# SeguidorC1_0.net
KiCad netlist of a schematic drawn in EAGLE
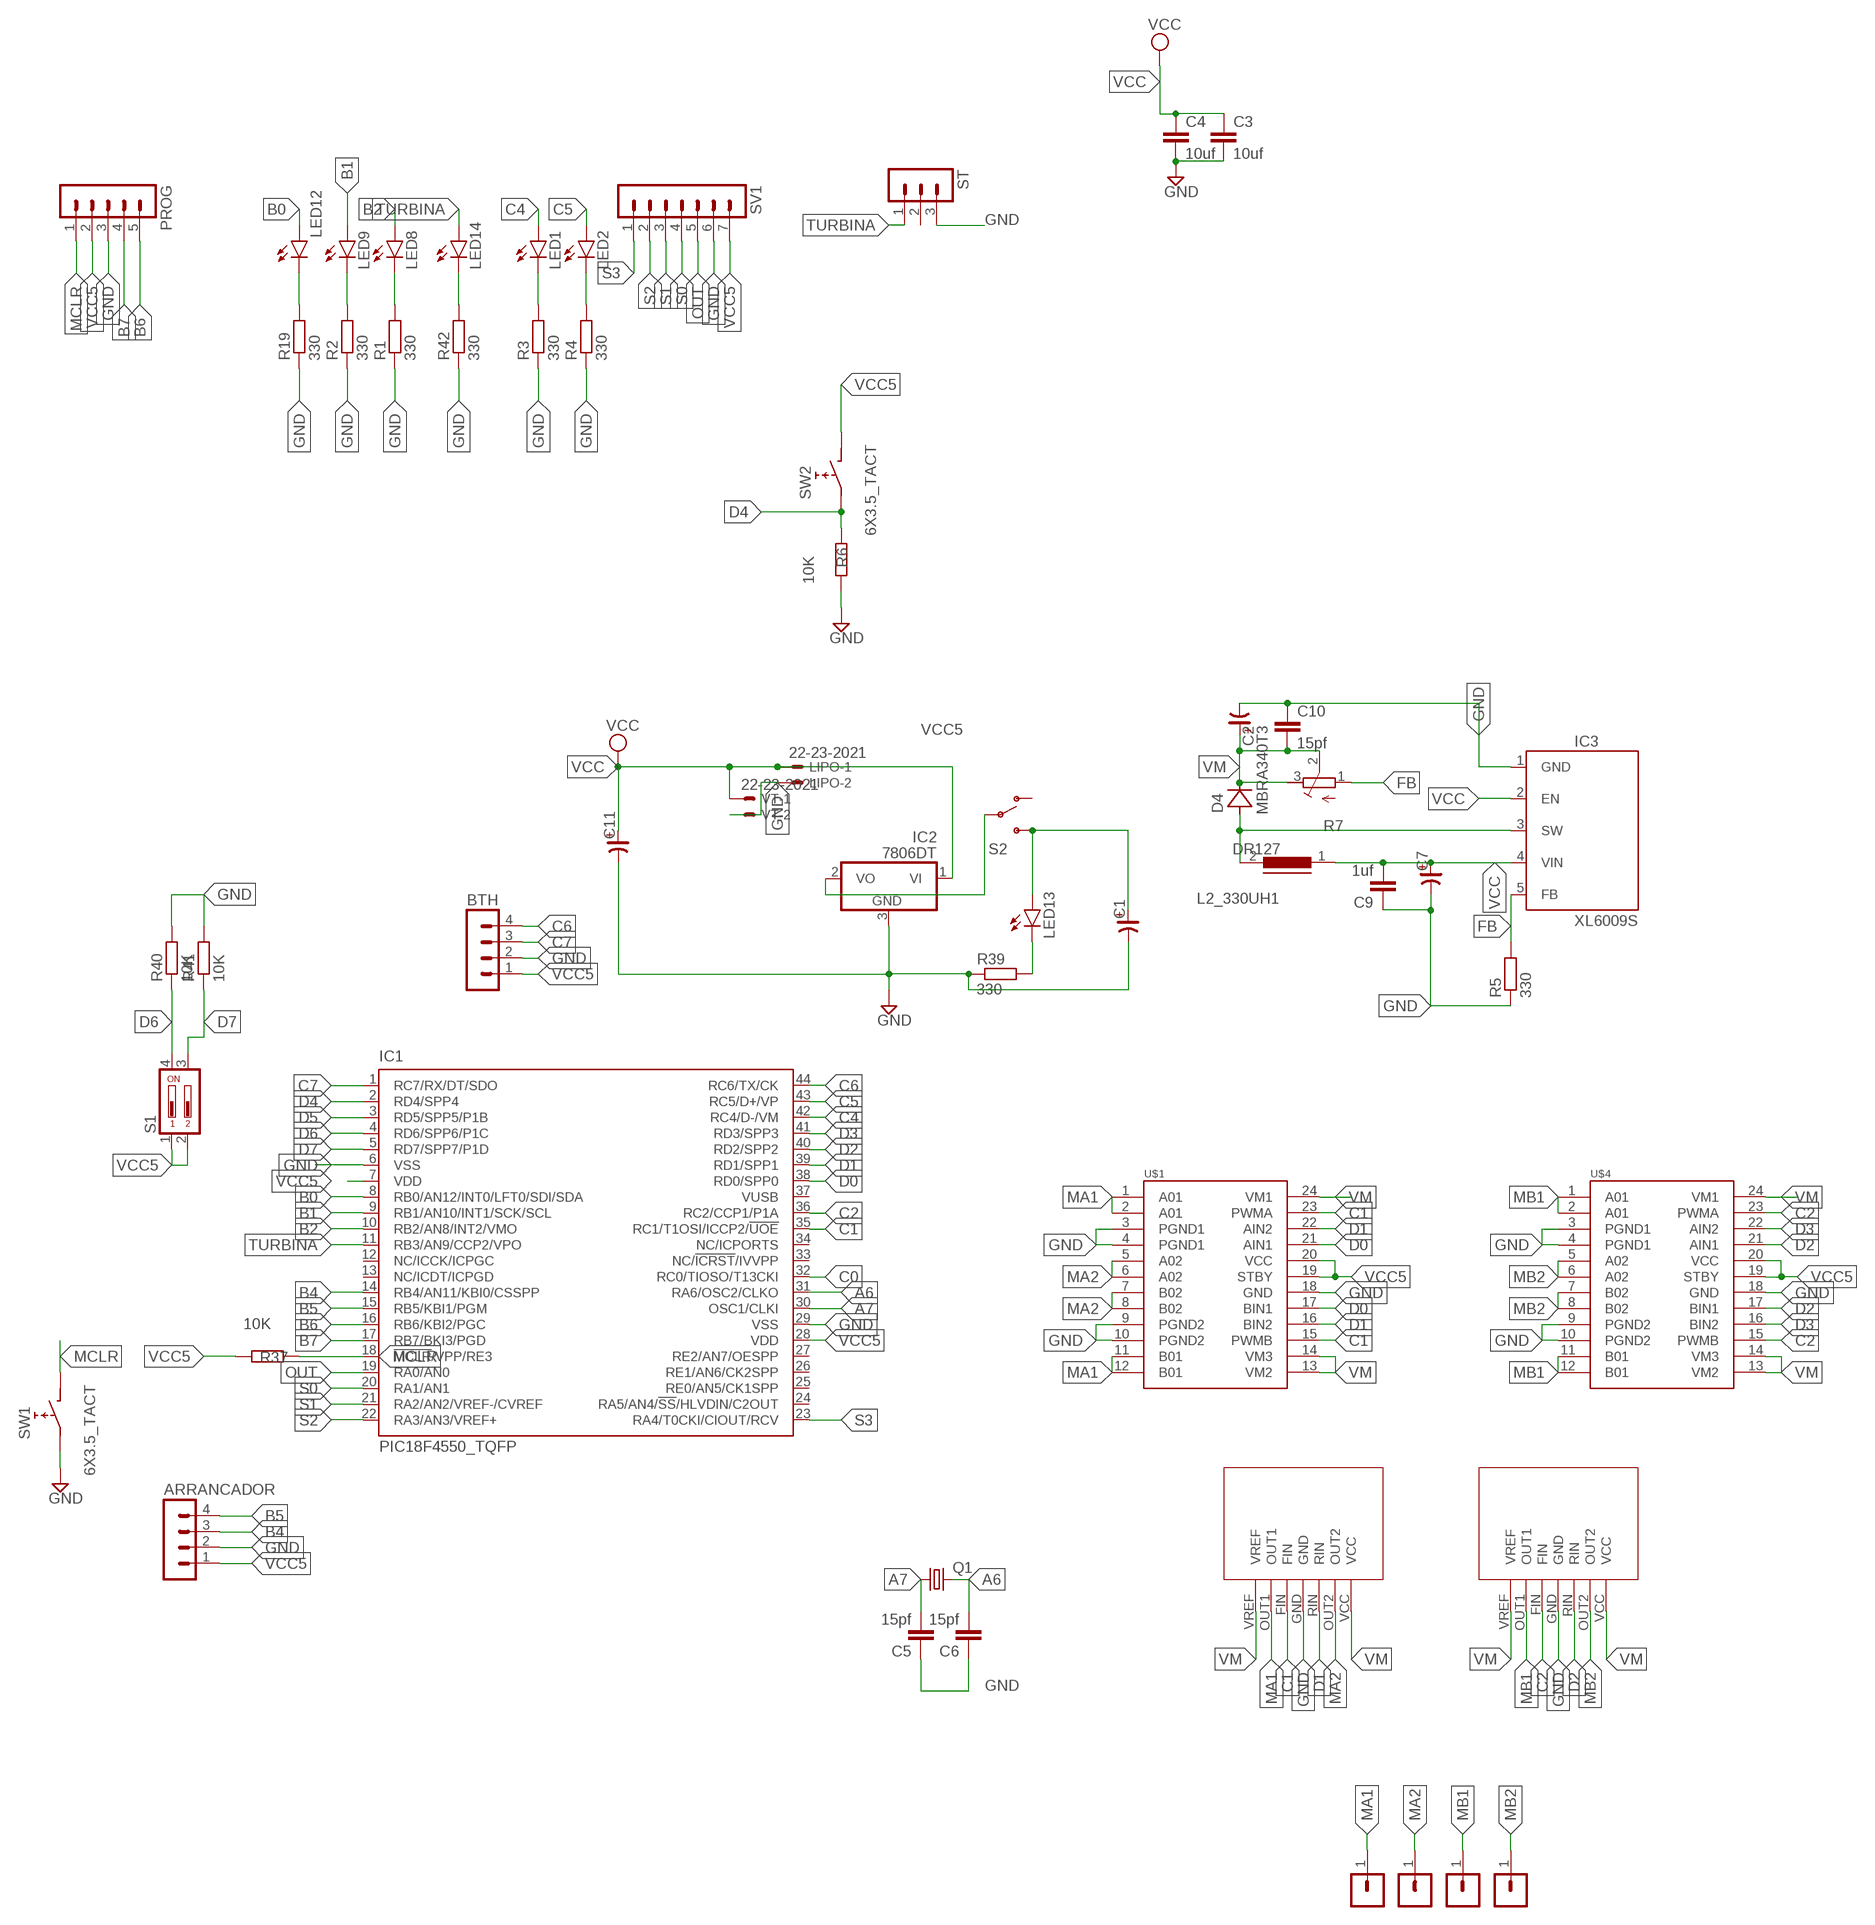
[diagram p0: schematic, sheet 1]

(export (version "E")
  (design (tool "Eeschema 10.0.6"))
  (components
    (comp (ref "ARRANCADOR")
      (value "MA04-1")
      (footprint "eagle-import:MA04-1")
      (libsource (lib "eagle-import") (part "MA04-1"))
    )
    (comp (ref "BTH")
      (value "MA04-1")
      (footprint "eagle-import:MA04-1")
      (libsource (lib "eagle-import") (part "MA04-1"))
    )
    (comp (ref "C1")
      (value "CP_SV-D")
      (footprint "eagle-import:CSV-D")
      (libsource (lib "eagle-import") (part "CP_SV-D"))
    )
    (comp (ref "C2")
      (value "CP_SV-D")
      (footprint "eagle-import:CSV-D")
      (libsource (lib "eagle-import") (part "CP_SV-D"))
    )
    (comp (ref "C3")
      (value "10uf")
      (footprint "eagle-import:C0805")
      (libsource (lib "eagle-import") (part "C-EUC0805"))
    )
    (comp (ref "C4")
      (value "10uf")
      (footprint "eagle-import:C0805")
      (libsource (lib "eagle-import") (part "C-EUC0805"))
    )
    (comp (ref "C5")
      (value "15pf")
      (footprint "eagle-import:C0805")
      (libsource (lib "eagle-import") (part "C-EUC0805"))
    )
    (comp (ref "C6")
      (value "15pf")
      (footprint "eagle-import:C0805")
      (libsource (lib "eagle-import") (part "C-EUC0805"))
    )
    (comp (ref "C7")
      (value "CP_SV-D")
      (footprint "eagle-import:CSV-D")
      (libsource (lib "eagle-import") (part "CP_SV-D"))
    )
    (comp (ref "C9")
      (value "1uf")
      (footprint "eagle-import:C0805")
      (libsource (lib "eagle-import") (part "C-EUC0805"))
    )
    (comp (ref "C10")
      (value "15pf")
      (footprint "eagle-import:C0805")
      (libsource (lib "eagle-import") (part "C-EUC0805"))
    )
    (comp (ref "C11")
      (value "CP_SV-D")
      (footprint "eagle-import:CSV-D")
      (fields (field (name "SPICEPREFIX") "C"))
      (libsource (lib "eagle-import") (part "CP_SV-D"))
    )
    (comp (ref "D4")
      (value "MBRA340T3")
      (footprint "eagle-import:SMA")
      (libsource (lib "eagle-import") (part "MBRA340T3"))
    )
    (comp (ref "IC1")
      (value "PIC18F4550_TQFP")
      (footprint "eagle-import:TQFP44")
      (fields (field (name "MF") "MICROCHIP") (field (name "MPN") "PIC18F4550-I/PT"))
      (libsource (lib "eagle-import") (part "PIC18F4_TQFP550"))
    )
    (comp (ref "IC2")
      (value "7806DT")
      (footprint "eagle-import:TO252")
      (libsource (lib "eagle-import") (part "78DT06"))
    )
    (comp (ref "IC3")
      (value "XL6009S")
      (footprint "eagle-import:TO263-5")
      (libsource (lib "eagle-import") (part "XL6009S"))
    )
    (comp (ref "L2_330UH1")
      (value "DR127")
      (footprint "eagle-import:DR127")
      (libsource (lib "eagle-import") (part "DR127"))
    )
    (comp (ref "LED1")
      (value "LEDCHIP-LED0805")
      (footprint "eagle-import:CHIP-LED0805")
      (libsource (lib "eagle-import") (part "LEDCHIP-LED0805"))
    )
    (comp (ref "LED2")
      (value "LEDCHIP-LED0805")
      (footprint "eagle-import:CHIP-LED0805")
      (libsource (lib "eagle-import") (part "LEDCHIP-LED0805"))
    )
    (comp (ref "LED8")
      (value "LEDCHIP-LED0805")
      (footprint "eagle-import:CHIP-LED0805")
      (libsource (lib "eagle-import") (part "LEDCHIP-LED0805"))
    )
    (comp (ref "LED9")
      (value "LEDCHIP-LED0805")
      (footprint "eagle-import:CHIP-LED0805")
      (libsource (lib "eagle-import") (part "LEDCHIP-LED0805"))
    )
    (comp (ref "LED12")
      (value "LEDCHIP-LED0805")
      (footprint "eagle-import:CHIP-LED0805")
      (libsource (lib "eagle-import") (part "LEDCHIP-LED0805"))
    )
    (comp (ref "LED13")
      (value "LEDCHIP-LED0805")
      (footprint "eagle-import:CHIP-LED0805")
      (libsource (lib "eagle-import") (part "LEDCHIP-LED0805"))
    )
    (comp (ref "LED14")
      (value "LEDCHIP-LED0805")
      (footprint "eagle-import:CHIP-LED0805")
      (libsource (lib "eagle-import") (part "LEDCHIP-LED0805"))
    )
    (comp (ref "LIPO")
      (value "22-23-2021")
      (footprint "eagle-import:22-23-2021")
      (fields (field (name "MF") "MOLEX"))
      (libsource (lib "eagle-import") (part "22-23-2021"))
    )
    (comp (ref "PROG")
      (value "MA05-1")
      (footprint "eagle-import:MA05-1")
      (libsource (lib "eagle-import") (part "MA05-1"))
    )
    (comp (ref "Q1")
      (value "CRYSTALHC49U-V")
      (footprint "eagle-import:HC49U-V")
      (libsource (lib "eagle-import") (part "CRYSTALHC49U-V"))
    )
    (comp (ref "R1")
      (value "330")
      (footprint "eagle-import:R0805")
      (libsource (lib "eagle-import") (part "resistor_348_R-EU_R0805"))
    )
    (comp (ref "R2")
      (value "330")
      (footprint "eagle-import:R0805")
      (libsource (lib "eagle-import") (part "resistor_348_R-EU_R0805"))
    )
    (comp (ref "R3")
      (value "330")
      (footprint "eagle-import:R0805")
      (libsource (lib "eagle-import") (part "resistor_348_R-EU_R0805"))
    )
    (comp (ref "R4")
      (value "330")
      (footprint "eagle-import:R0805")
      (libsource (lib "eagle-import") (part "resistor_348_R-EU_R0805"))
    )
    (comp (ref "R5")
      (value "330")
      (footprint "eagle-import:R0805")
      (libsource (lib "eagle-import") (part "resistor_348_R-EU_R0805"))
    )
    (comp (ref "R6")
      (value "10K")
      (footprint "eagle-import:R0805W")
      (libsource (lib "eagle-import") (part "R-EU_R0805W"))
    )
    (comp (ref "R7")
      (value "R-TRIMM3296W")
      (footprint "eagle-import:RTRIM3296W")
      (libsource (lib "eagle-import") (part "R-TRIMM3296W"))
    )
    (comp (ref "R19")
      (value "330")
      (footprint "eagle-import:R0805")
      (libsource (lib "eagle-import") (part "resistor_348_R-EU_R0805"))
    )
    (comp (ref "R37")
      (value "10K")
      (footprint "eagle-import:R0805W")
      (libsource (lib "eagle-import") (part "R-EU_R0805W"))
    )
    (comp (ref "R39")
      (value "330")
      (footprint "eagle-import:R0805")
      (libsource (lib "eagle-import") (part "resistor_348_R-EU_R0805"))
    )
    (comp (ref "R40")
      (value "10K")
      (footprint "eagle-import:R0805W")
      (libsource (lib "eagle-import") (part "R-EU_R0805W"))
    )
    (comp (ref "R41")
      (value "10K")
      (footprint "eagle-import:R0805W")
      (libsource (lib "eagle-import") (part "R-EU_R0805W"))
    )
    (comp (ref "R42")
      (value "330")
      (footprint "eagle-import:R0805")
      (libsource (lib "eagle-import") (part "resistor_348_R-EU_R0805"))
    )
    (comp (ref "S1")
      (value "DIP02YL")
      (footprint "eagle-import:DIP02YL")
      (libsource (lib "eagle-import") (part "DIP02YL"))
    )
    (comp (ref "S2")
      (value "SWITCH-SPSTPTH")
      (footprint "eagle-import:SWITCH-SPDT")
      (libsource (lib "eagle-import") (part "SWITCH-SPSTPTH"))
    )
    (comp (ref "ST")
      (value "MA03-1")
      (footprint "eagle-import:MA03-1")
      (libsource (lib "eagle-import") (part "MA03-1"))
    )
    (comp (ref "SV1")
      (value "MA07-1")
      (footprint "eagle-import:MA07-1")
      (libsource (lib "eagle-import") (part "MA07-1"))
    )
    (comp (ref "SV3")
      (value "MA01-1")
      (footprint "eagle-import:MA01-1")
      (libsource (lib "eagle-import") (part "MA01-1"))
    )
    (comp (ref "SV4")
      (value "MA01-1")
      (footprint "eagle-import:MA01-1")
      (libsource (lib "eagle-import") (part "MA01-1"))
    )
    (comp (ref "SV5")
      (value "MA01-1")
      (footprint "eagle-import:MA01-1")
      (libsource (lib "eagle-import") (part "MA01-1"))
    )
    (comp (ref "SV6")
      (value "MA01-1")
      (footprint "eagle-import:MA01-1")
      (libsource (lib "eagle-import") (part "MA01-1"))
    )
    (comp (ref "SW1")
      (value "6X3.5_TACT")
      (footprint "eagle-import:TACT_6X3.5")
      (libsource (lib "eagle-import") (part "6X3.5_TACT"))
    )
    (comp (ref "SW2")
      (value "6X3.5_TACT")
      (footprint "eagle-import:TACT_6X3.5")
      (libsource (lib "eagle-import") (part "6X3.5_TACT"))
    )
    (comp (ref "U$1")
      (value "TB6621FNG")
      (footprint "eagle-import:SSOP24")
      (libsource (lib "eagle-import") (part "TB6621FNG"))
    )
    (comp (ref "U$2")
      (value "BD623XXX")
      (footprint "eagle-import:HRP7")
      (libsource (lib "eagle-import") (part "BD623XXX"))
    )
    (comp (ref "U$3")
      (value "BD623XXX")
      (footprint "eagle-import:HRP7")
      (libsource (lib "eagle-import") (part "BD623XXX"))
    )
    (comp (ref "U$4")
      (value "TB6621FNG")
      (footprint "eagle-import:SSOP24")
      (libsource (lib "eagle-import") (part "TB6621FNG"))
    )
    (comp (ref "VT")
      (value "22-23-2021")
      (footprint "eagle-import:22-23-2021")
      (fields (field (name "MF") "MOLEX"))
      (libsource (lib "eagle-import") (part "22-23-2021"))
    )
  )
  (nets
    (net (code "1") (name "A6") (class "Default")
      (node (ref "C6") (pin "2") (pinfunction "2_2") (pintype "passive"))
      (node (ref "IC1") (pin "31") (pinfunction "RA6/OSC2/CLKO_31") (pintype "output"))
      (node (ref "Q1") (pin "2") (pinfunction "2_2") (pintype "passive"))
    )
    (net (code "2") (name "A7") (class "Default")
      (node (ref "C5") (pin "2") (pinfunction "2_2") (pintype "passive"))
      (node (ref "IC1") (pin "30") (pinfunction "OSC1/CLKI_30") (pintype "input"))
      (node (ref "Q1") (pin "1") (pinfunction "1_1") (pintype "passive"))
    )
    (net (code "3") (name "B0") (class "Default")
      (node (ref "IC1") (pin "8") (pinfunction "RB0/AN12/INT0/LFT0/SDI/SDA_8") (pintype "bidirectional"))
      (node (ref "LED12") (pin "A") (pinfunction "A_A") (pintype "passive"))
    )
    (net (code "4") (name "B1") (class "Default")
      (node (ref "IC1") (pin "9") (pinfunction "RB1/AN10/INT1/SCK/SCL_9") (pintype "bidirectional"))
      (node (ref "LED9") (pin "A") (pinfunction "A_A") (pintype "passive"))
    )
    (net (code "5") (name "B2") (class "Default")
      (node (ref "IC1") (pin "10") (pinfunction "RB2/AN8/INT2/VMO_10") (pintype "bidirectional"))
      (node (ref "LED8") (pin "A") (pinfunction "A_A") (pintype "passive"))
    )
    (net (code "6") (name "B4") (class "Default")
      (node (ref "ARRANCADOR") (pin "3") (pinfunction "3_3") (pintype "passive"))
      (node (ref "IC1") (pin "14") (pinfunction "RB4/AN11/KBI0/CSSPP_14") (pintype "bidirectional"))
    )
    (net (code "7") (name "B5") (class "Default")
      (node (ref "ARRANCADOR") (pin "4") (pinfunction "4_4") (pintype "passive"))
      (node (ref "IC1") (pin "15") (pinfunction "RB5/KBI1/PGM_15") (pintype "bidirectional"))
    )
    (net (code "8") (name "B6") (class "Default")
      (node (ref "IC1") (pin "16") (pinfunction "RB6/KBI2/PGC_16") (pintype "bidirectional"))
      (node (ref "PROG") (pin "5") (pinfunction "5_5") (pintype "passive"))
    )
    (net (code "9") (name "B7") (class "Default")
      (node (ref "IC1") (pin "17") (pinfunction "RB7/BKI3/PGD_17") (pintype "bidirectional"))
      (node (ref "PROG") (pin "4") (pinfunction "4_4") (pintype "passive"))
    )
    (net (code "10") (name "C0") (class "Default")
      (node (ref "IC1") (pin "32") (pinfunction "RC0/TIOSO/T13CKI_32") (pintype "bidirectional"))
    )
    (net (code "11") (name "C1") (class "Default")
      (node (ref "IC1") (pin "35") (pinfunction "RC1/T1OSI/ICCP2/~{UOE}_35") (pintype "bidirectional"))
      (node (ref "U$1") (pin "15") (pinfunction "PWMB_15") (pintype "bidirectional"))
      (node (ref "U$1") (pin "23") (pinfunction "PWMA_23") (pintype "bidirectional"))
      (node (ref "U$2") (pin "FIN") (pinfunction "FIN_FIN") (pintype "bidirectional"))
    )
    (net (code "12") (name "C2") (class "Default")
      (node (ref "IC1") (pin "36") (pinfunction "RC2/CCP1/P1A_36") (pintype "bidirectional"))
      (node (ref "U$3") (pin "FIN") (pinfunction "FIN_FIN") (pintype "bidirectional"))
      (node (ref "U$4") (pin "15") (pinfunction "PWMB_15") (pintype "bidirectional"))
      (node (ref "U$4") (pin "23") (pinfunction "PWMA_23") (pintype "bidirectional"))
    )
    (net (code "13") (name "C4") (class "Default")
      (node (ref "IC1") (pin "42") (pinfunction "RC4/D-/VM_42") (pintype "bidirectional"))
      (node (ref "LED1") (pin "A") (pinfunction "A_A") (pintype "passive"))
    )
    (net (code "14") (name "C5") (class "Default")
      (node (ref "IC1") (pin "43") (pinfunction "RC5/D+/VP_43") (pintype "bidirectional"))
      (node (ref "LED2") (pin "A") (pinfunction "A_A") (pintype "passive"))
    )
    (net (code "15") (name "C6") (class "Default")
      (node (ref "BTH") (pin "4") (pinfunction "4_4") (pintype "passive"))
      (node (ref "IC1") (pin "44") (pinfunction "RC6/TX/CK_44") (pintype "bidirectional"))
    )
    (net (code "16") (name "C7") (class "Default")
      (node (ref "BTH") (pin "3") (pinfunction "3_3") (pintype "passive"))
      (node (ref "IC1") (pin "1") (pinfunction "RC7/RX/DT/SDO_1") (pintype "bidirectional"))
    )
    (net (code "17") (name "D0") (class "Default")
      (node (ref "IC1") (pin "38") (pinfunction "RD0/SPP0_38") (pintype "bidirectional"))
      (node (ref "U$1") (pin "17") (pinfunction "BIN1_17") (pintype "bidirectional"))
      (node (ref "U$1") (pin "21") (pinfunction "AIN1_21") (pintype "bidirectional"))
    )
    (net (code "18") (name "D1") (class "Default")
      (node (ref "IC1") (pin "39") (pinfunction "RD1/SPP1_39") (pintype "bidirectional"))
      (node (ref "U$1") (pin "16") (pinfunction "BIN2_16") (pintype "bidirectional"))
      (node (ref "U$1") (pin "22") (pinfunction "AIN2_22") (pintype "bidirectional"))
      (node (ref "U$2") (pin "RIN") (pinfunction "RIN_RIN") (pintype "bidirectional"))
    )
    (net (code "19") (name "D2") (class "Default")
      (node (ref "IC1") (pin "40") (pinfunction "RD2/SPP2_40") (pintype "bidirectional"))
      (node (ref "U$3") (pin "RIN") (pinfunction "RIN_RIN") (pintype "bidirectional"))
      (node (ref "U$4") (pin "17") (pinfunction "BIN1_17") (pintype "bidirectional"))
      (node (ref "U$4") (pin "21") (pinfunction "AIN1_21") (pintype "bidirectional"))
    )
    (net (code "20") (name "D3") (class "Default")
      (node (ref "IC1") (pin "41") (pinfunction "RD3/SPP3_41") (pintype "bidirectional"))
      (node (ref "U$4") (pin "16") (pinfunction "BIN2_16") (pintype "bidirectional"))
      (node (ref "U$4") (pin "22") (pinfunction "AIN2_22") (pintype "bidirectional"))
    )
    (net (code "21") (name "D4") (class "Default")
      (node (ref "IC1") (pin "2") (pinfunction "RD4/SPP4_2") (pintype "bidirectional"))
      (node (ref "R6") (pin "2") (pinfunction "2_2") (pintype "passive"))
      (node (ref "SW2") (pin "P$1") (pinfunction "1_P$1") (pintype "passive"))
    )
    (net (code "22") (name "D5") (class "Default")
      (node (ref "IC1") (pin "3") (pinfunction "RD5/SPP5/P1B_3") (pintype "bidirectional"))
    )
    (net (code "23") (name "D6") (class "Default")
      (node (ref "IC1") (pin "4") (pinfunction "RD6/SPP6/P1C_4") (pintype "bidirectional"))
      (node (ref "R40") (pin "1") (pinfunction "1_1") (pintype "passive"))
      (node (ref "S1") (pin "4") (pinfunction "4_4") (pintype "passive"))
    )
    (net (code "24") (name "D7") (class "Default")
      (node (ref "IC1") (pin "5") (pinfunction "RD7/SPP7/P1D_5") (pintype "bidirectional"))
      (node (ref "R41") (pin "1") (pinfunction "1_1") (pintype "passive"))
      (node (ref "S1") (pin "3") (pinfunction "3_3") (pintype "passive"))
    )
    (net (code "25") (name "FB") (class "Default")
      (node (ref "IC3") (pin "5") (pinfunction "FB_5") (pintype "output"))
      (node (ref "R5") (pin "2") (pinfunction "2_2") (pintype "passive"))
      (node (ref "R7") (pin "1") (pinfunction "A_1") (pintype "passive"))
    )
    (net (code "26") (name "GND") (class "Default")
      (node (ref "ARRANCADOR") (pin "2") (pinfunction "2_2") (pintype "passive"))
      (node (ref "BTH") (pin "2") (pinfunction "2_2") (pintype "passive"))
      (node (ref "C1") (pin "-") (pinfunction "-_-") (pintype "passive"))
      (node (ref "C10") (pin "1") (pinfunction "1_1") (pintype "passive"))
      (node (ref "C11") (pin "-") (pinfunction "-_-") (pintype "passive"))
      (node (ref "C2") (pin "-") (pinfunction "-_-") (pintype "passive"))
      (node (ref "C3") (pin "2") (pinfunction "2_2") (pintype "passive"))
      (node (ref "C4") (pin "2") (pinfunction "2_2") (pintype "passive"))
      (node (ref "C5") (pin "1") (pinfunction "1_1") (pintype "passive"))
      (node (ref "C6") (pin "1") (pinfunction "1_1") (pintype "passive"))
      (node (ref "C7") (pin "-") (pinfunction "-_-") (pintype "passive"))
      (node (ref "C9") (pin "1") (pinfunction "1_1") (pintype "passive"))
      (node (ref "IC1") (pin "29") (pinfunction "VSS_29") (pintype "power_in"))
      (node (ref "IC1") (pin "6") (pinfunction "VSS_6") (pintype "power_in"))
      (node (ref "IC2") (pin "3") (pinfunction "GND_3") (pintype "passive"))
      (node (ref "IC3") (pin "1") (pinfunction "GND_1") (pintype "input"))
      (node (ref "LIPO") (pin "2") (pinfunction "S_2") (pintype "passive"))
      (node (ref "PROG") (pin "3") (pinfunction "3_3") (pintype "passive"))
      (node (ref "R1") (pin "1") (pinfunction "1_1") (pintype "passive"))
      (node (ref "R19") (pin "1") (pinfunction "1_1") (pintype "passive"))
      (node (ref "R2") (pin "1") (pinfunction "1_1") (pintype "passive"))
      (node (ref "R3") (pin "1") (pinfunction "1_1") (pintype "passive"))
      (node (ref "R39") (pin "1") (pinfunction "1_1") (pintype "passive"))
      (node (ref "R4") (pin "1") (pinfunction "1_1") (pintype "passive"))
      (node (ref "R40") (pin "2") (pinfunction "2_2") (pintype "passive"))
      (node (ref "R41") (pin "2") (pinfunction "2_2") (pintype "passive"))
      (node (ref "R42") (pin "1") (pinfunction "1_1") (pintype "passive"))
      (node (ref "R5") (pin "1") (pinfunction "1_1") (pintype "passive"))
      (node (ref "R6") (pin "1") (pinfunction "1_1") (pintype "passive"))
      (node (ref "ST") (pin "3") (pinfunction "3_3") (pintype "passive"))
      (node (ref "SV1") (pin "6") (pinfunction "6_6") (pintype "passive"))
      (node (ref "SW1") (pin "P$1") (pinfunction "1_P$1") (pintype "passive"))
      (node (ref "U$1") (pin "10") (pinfunction "PGND2_10") (pintype "bidirectional"))
      (node (ref "U$1") (pin "18") (pinfunction "GND_18") (pintype "bidirectional"))
      (node (ref "U$1") (pin "3") (pinfunction "PGND1_3") (pintype "bidirectional"))
      (node (ref "U$1") (pin "4") (pinfunction "PGND1_4") (pintype "bidirectional"))
      (node (ref "U$1") (pin "9") (pinfunction "PGND2_9") (pintype "bidirectional"))
      (node (ref "U$2") (pin "GND") (pinfunction "GND_GND") (pintype "bidirectional"))
      (node (ref "U$3") (pin "GND") (pinfunction "GND_GND") (pintype "bidirectional"))
      (node (ref "U$4") (pin "10") (pinfunction "PGND2_10") (pintype "bidirectional"))
      (node (ref "U$4") (pin "18") (pinfunction "GND_18") (pintype "bidirectional"))
      (node (ref "U$4") (pin "3") (pinfunction "PGND1_3") (pintype "bidirectional"))
      (node (ref "U$4") (pin "4") (pinfunction "PGND1_4") (pintype "bidirectional"))
      (node (ref "U$4") (pin "9") (pinfunction "PGND2_9") (pintype "bidirectional"))
      (node (ref "VT") (pin "2") (pinfunction "S_2") (pintype "passive"))
    )
    (net (code "27") (name "MA1") (class "Default")
      (node (ref "SV3") (pin "1") (pinfunction "3_1") (pintype "passive"))
      (node (ref "U$1") (pin "1") (pinfunction "A01_1") (pintype "bidirectional"))
      (node (ref "U$1") (pin "11") (pinfunction "B01_11") (pintype "bidirectional"))
      (node (ref "U$1") (pin "12") (pinfunction "B01_12") (pintype "bidirectional"))
      (node (ref "U$1") (pin "2") (pinfunction "A01_2") (pintype "bidirectional"))
      (node (ref "U$2") (pin "OUT1") (pinfunction "OUT1_OUT1") (pintype "bidirectional"))
    )
    (net (code "28") (name "MA2") (class "Default")
      (node (ref "SV4") (pin "1") (pinfunction "3_1") (pintype "passive"))
      (node (ref "U$1") (pin "5") (pinfunction "A02_5") (pintype "bidirectional"))
      (node (ref "U$1") (pin "6") (pinfunction "A02_6") (pintype "bidirectional"))
      (node (ref "U$1") (pin "7") (pinfunction "B02_7") (pintype "bidirectional"))
      (node (ref "U$1") (pin "8") (pinfunction "B02_8") (pintype "bidirectional"))
      (node (ref "U$2") (pin "OUT2") (pinfunction "OUT2_OUT2") (pintype "bidirectional"))
    )
    (net (code "29") (name "MB1") (class "Default")
      (node (ref "SV5") (pin "1") (pinfunction "3_1") (pintype "passive"))
      (node (ref "U$3") (pin "OUT1") (pinfunction "OUT1_OUT1") (pintype "bidirectional"))
      (node (ref "U$4") (pin "1") (pinfunction "A01_1") (pintype "bidirectional"))
      (node (ref "U$4") (pin "11") (pinfunction "B01_11") (pintype "bidirectional"))
      (node (ref "U$4") (pin "12") (pinfunction "B01_12") (pintype "bidirectional"))
      (node (ref "U$4") (pin "2") (pinfunction "A01_2") (pintype "bidirectional"))
    )
    (net (code "30") (name "MB2") (class "Default")
      (node (ref "SV6") (pin "1") (pinfunction "3_1") (pintype "passive"))
      (node (ref "U$3") (pin "OUT2") (pinfunction "OUT2_OUT2") (pintype "bidirectional"))
      (node (ref "U$4") (pin "5") (pinfunction "A02_5") (pintype "bidirectional"))
      (node (ref "U$4") (pin "6") (pinfunction "A02_6") (pintype "bidirectional"))
      (node (ref "U$4") (pin "7") (pinfunction "B02_7") (pintype "bidirectional"))
      (node (ref "U$4") (pin "8") (pinfunction "B02_8") (pintype "bidirectional"))
    )
    (net (code "31") (name "MCLR") (class "Default")
      (node (ref "IC1") (pin "18") (pinfunction "~{MCLR}/VPP/RE3_18") (pintype "input"))
      (node (ref "PROG") (pin "1") (pinfunction "1_1") (pintype "passive"))
      (node (ref "R37") (pin "2") (pinfunction "2_2") (pintype "passive"))
      (node (ref "SW1") (pin "P$2") (pinfunction "2_P$2") (pintype "passive"))
    )
    (net (code "32") (name "Net-(IC2-VO)") (class "Default")
      (node (ref "IC2") (pin "2") (pinfunction "VO_2") (pintype "passive"))
      (node (ref "S2") (pin "2") (pinfunction "P_2") (pintype "passive"))
    )
    (net (code "33") (name "Net-(IC3-SW)") (class "Default")
      (node (ref "D4") (pin "A") (pinfunction "A_A") (pintype "passive"))
      (node (ref "IC3") (pin "3") (pinfunction "SW_3") (pintype "power_in"))
      (node (ref "L2_330UH1") (pin "2") (pinfunction "2_2") (pintype "passive"))
    )
    (net (code "34") (name "Net-(LED1-PadC)") (class "Default")
      (node (ref "LED1") (pin "C") (pinfunction "C_C") (pintype "passive"))
      (node (ref "R3") (pin "2") (pinfunction "2_2") (pintype "passive"))
    )
    (net (code "35") (name "Net-(LED2-PadC)") (class "Default")
      (node (ref "LED2") (pin "C") (pinfunction "C_C") (pintype "passive"))
      (node (ref "R4") (pin "2") (pinfunction "2_2") (pintype "passive"))
    )
    (net (code "36") (name "Net-(LED8-PadC)") (class "Default")
      (node (ref "LED8") (pin "C") (pinfunction "C_C") (pintype "passive"))
      (node (ref "R1") (pin "2") (pinfunction "2_2") (pintype "passive"))
    )
    (net (code "37") (name "Net-(LED9-PadC)") (class "Default")
      (node (ref "LED9") (pin "C") (pinfunction "C_C") (pintype "passive"))
      (node (ref "R2") (pin "2") (pinfunction "2_2") (pintype "passive"))
    )
    (net (code "38") (name "Net-(LED12-PadC)") (class "Default")
      (node (ref "LED12") (pin "C") (pinfunction "C_C") (pintype "passive"))
      (node (ref "R19") (pin "2") (pinfunction "2_2") (pintype "passive"))
    )
    (net (code "39") (name "Net-(LED13-PadC)") (class "Default")
      (node (ref "LED13") (pin "C") (pinfunction "C_C") (pintype "passive"))
      (node (ref "R39") (pin "2") (pinfunction "2_2") (pintype "passive"))
    )
    (net (code "40") (name "Net-(LED14-PadC)") (class "Default")
      (node (ref "LED14") (pin "C") (pinfunction "C_C") (pintype "passive"))
      (node (ref "R42") (pin "2") (pinfunction "2_2") (pintype "passive"))
    )
    (net (code "41") (name "OUT") (class "Default")
      (node (ref "IC1") (pin "19") (pinfunction "RA0/AN0_19") (pintype "bidirectional"))
      (node (ref "SV1") (pin "5") (pinfunction "5_5") (pintype "passive"))
    )
    (net (code "42") (name "S0") (class "Default")
      (node (ref "IC1") (pin "20") (pinfunction "RA1/AN1_20") (pintype "bidirectional"))
      (node (ref "SV1") (pin "4") (pinfunction "4_4") (pintype "passive"))
    )
    (net (code "43") (name "S1") (class "Default")
      (node (ref "IC1") (pin "21") (pinfunction "RA2/AN2/VREF-/CVREF_21") (pintype "bidirectional"))
      (node (ref "SV1") (pin "3") (pinfunction "3_3") (pintype "passive"))
    )
    (net (code "44") (name "S2") (class "Default")
      (node (ref "IC1") (pin "22") (pinfunction "RA3/AN3/VREF+_22") (pintype "bidirectional"))
      (node (ref "SV1") (pin "2") (pinfunction "2_2") (pintype "passive"))
    )
    (net (code "45") (name "S3") (class "Default")
      (node (ref "IC1") (pin "23") (pinfunction "RA4/T0CKI/CIOUT/RCV_23") (pintype "bidirectional"))
      (node (ref "SV1") (pin "1") (pinfunction "1_1") (pintype "passive"))
    )
    (net (code "46") (name "TURBINA") (class "Default")
      (node (ref "IC1") (pin "11") (pinfunction "RB3/AN9/CCP2/VPO_11") (pintype "bidirectional"))
      (node (ref "LED14") (pin "A") (pinfunction "A_A") (pintype "passive"))
      (node (ref "ST") (pin "1") (pinfunction "1_1") (pintype "passive"))
    )
    (net (code "47") (name "VCC") (class "Default")
      (node (ref "C11") (pin "+") (pinfunction "+_+") (pintype "passive"))
      (node (ref "C3") (pin "1") (pinfunction "1_1") (pintype "passive"))
      (node (ref "C4") (pin "1") (pinfunction "1_1") (pintype "passive"))
      (node (ref "C7") (pin "+") (pinfunction "+_+") (pintype "passive"))
      (node (ref "C9") (pin "2") (pinfunction "2_2") (pintype "passive"))
      (node (ref "IC2") (pin "1") (pinfunction "VI_1") (pintype "input"))
      (node (ref "IC3") (pin "2") (pinfunction "EN_2") (pintype "input"))
      (node (ref "IC3") (pin "4") (pinfunction "VIN_4") (pintype "power_in"))
      (node (ref "L2_330UH1") (pin "1") (pinfunction "1_1") (pintype "passive"))
      (node (ref "LIPO") (pin "1") (pinfunction "S_1") (pintype "passive"))
      (node (ref "VT") (pin "1") (pinfunction "S_1") (pintype "passive"))
    )
    (net (code "48") (name "VCC5") (class "Default")
      (node (ref "ARRANCADOR") (pin "1") (pinfunction "1_1") (pintype "passive"))
      (node (ref "BTH") (pin "1") (pinfunction "1_1") (pintype "passive"))
      (node (ref "C1") (pin "+") (pinfunction "+_+") (pintype "passive"))
      (node (ref "IC1") (pin "28") (pinfunction "VDD_28") (pintype "power_in"))
      (node (ref "IC1") (pin "7") (pinfunction "VDD_7") (pintype "power_in"))
      (node (ref "LED13") (pin "A") (pinfunction "A_A") (pintype "passive"))
      (node (ref "PROG") (pin "2") (pinfunction "2_2") (pintype "passive"))
      (node (ref "R37") (pin "1") (pinfunction "1_1") (pintype "passive"))
      (node (ref "S1") (pin "1") (pinfunction "1_1") (pintype "passive"))
      (node (ref "S1") (pin "2") (pinfunction "2_2") (pintype "passive"))
      (node (ref "S2") (pin "3") (pinfunction "S_3") (pintype "passive"))
      (node (ref "SV1") (pin "7") (pinfunction "7_7") (pintype "passive"))
      (node (ref "SW2") (pin "P$2") (pinfunction "2_P$2") (pintype "passive"))
      (node (ref "U$1") (pin "19") (pinfunction "STBY_19") (pintype "bidirectional"))
      (node (ref "U$1") (pin "20") (pinfunction "VCC_20") (pintype "bidirectional"))
      (node (ref "U$4") (pin "19") (pinfunction "STBY_19") (pintype "bidirectional"))
      (node (ref "U$4") (pin "20") (pinfunction "VCC_20") (pintype "bidirectional"))
    )
    (net (code "49") (name "VM") (class "Default")
      (node (ref "C10") (pin "2") (pinfunction "2_2") (pintype "passive"))
      (node (ref "C2") (pin "+") (pinfunction "+_+") (pintype "passive"))
      (node (ref "D4") (pin "C") (pinfunction "C_C") (pintype "passive"))
      (node (ref "R7") (pin "2") (pinfunction "S_2") (pintype "passive"))
      (node (ref "R7") (pin "3") (pinfunction "E_3") (pintype "passive"))
      (node (ref "U$1") (pin "13") (pinfunction "VM2_13") (pintype "bidirectional"))
      (node (ref "U$1") (pin "14") (pinfunction "VM3_14") (pintype "bidirectional"))
      (node (ref "U$1") (pin "24") (pinfunction "VM1_24") (pintype "bidirectional"))
      (node (ref "U$2") (pin "VCC") (pinfunction "VCC_VCC") (pintype "bidirectional"))
      (node (ref "U$2") (pin "VREF") (pinfunction "VREF_VREF") (pintype "bidirectional"))
      (node (ref "U$3") (pin "VCC") (pinfunction "VCC_VCC") (pintype "bidirectional"))
      (node (ref "U$3") (pin "VREF") (pinfunction "VREF_VREF") (pintype "bidirectional"))
      (node (ref "U$4") (pin "13") (pinfunction "VM2_13") (pintype "bidirectional"))
      (node (ref "U$4") (pin "14") (pinfunction "VM3_14") (pintype "bidirectional"))
      (node (ref "U$4") (pin "24") (pinfunction "VM1_24") (pintype "bidirectional"))
    )
    (net (code "50") (name "unconnected-(IC1-NC{slash}ICCK{slash}ICPGC-Pad12)") (class "Default")
      (node (ref "IC1") (pin "12") (pinfunction "NC/ICCK/ICPGC_12") (pintype "bidirectional"))
    )
    (net (code "51") (name "unconnected-(IC1-NC{slash}ICDT{slash}ICPGD-Pad13)") (class "Default")
      (node (ref "IC1") (pin "13") (pinfunction "NC/ICDT/ICPGD_13") (pintype "bidirectional"))
    )
    (net (code "52") (name "unconnected-(IC1-NC{slash}ICPORTS-Pad34)") (class "Default")
      (node (ref "IC1") (pin "34") (pinfunction "NC/ICPORTS_34") (pintype "input"))
    )
    (net (code "53") (name "unconnected-(IC1-NC{slash}~{ICRST}{slash}IVVPP-Pad33)") (class "Default")
      (node (ref "IC1") (pin "33") (pinfunction "NC/~{ICRST}/IVVPP_33") (pintype "input"))
    )
    (net (code "54") (name "unconnected-(IC1-RA5{slash}AN4{slash}~{SS}{slash}HLVDIN{slash}C2OUT-Pad24)") (class "Default")
      (node (ref "IC1") (pin "24") (pinfunction "RA5/AN4/~{SS}/HLVDIN/C2OUT_24") (pintype "bidirectional"))
    )
    (net (code "55") (name "unconnected-(IC1-RE0{slash}AN5{slash}CK1SPP-Pad25)") (class "Default")
      (node (ref "IC1") (pin "25") (pinfunction "RE0/AN5/CK1SPP_25") (pintype "bidirectional"))
    )
    (net (code "56") (name "unconnected-(IC1-RE1{slash}AN6{slash}CK2SPP-Pad26)") (class "Default")
      (node (ref "IC1") (pin "26") (pinfunction "RE1/AN6/CK2SPP_26") (pintype "bidirectional"))
    )
    (net (code "57") (name "unconnected-(IC1-RE2{slash}AN7{slash}OESPP-Pad27)") (class "Default")
      (node (ref "IC1") (pin "27") (pinfunction "RE2/AN7/OESPP_27") (pintype "bidirectional"))
    )
    (net (code "58") (name "unconnected-(IC1-VUSB-Pad37)") (class "Default")
      (node (ref "IC1") (pin "37") (pinfunction "VUSB_37") (pintype "bidirectional"))
    )
    (net (code "59") (name "unconnected-(S2-O-Pad1)") (class "Default")
      (node (ref "S2") (pin "1") (pinfunction "O_1") (pintype "passive"))
    )
    (net (code "60") (name "unconnected-(ST-Pad2)") (class "Default")
      (node (ref "ST") (pin "2") (pinfunction "2_2") (pintype "passive"))
    )
  )
)
